# HexaWall-v1.net
KiCad netlist of a schematic drawn in EAGLE
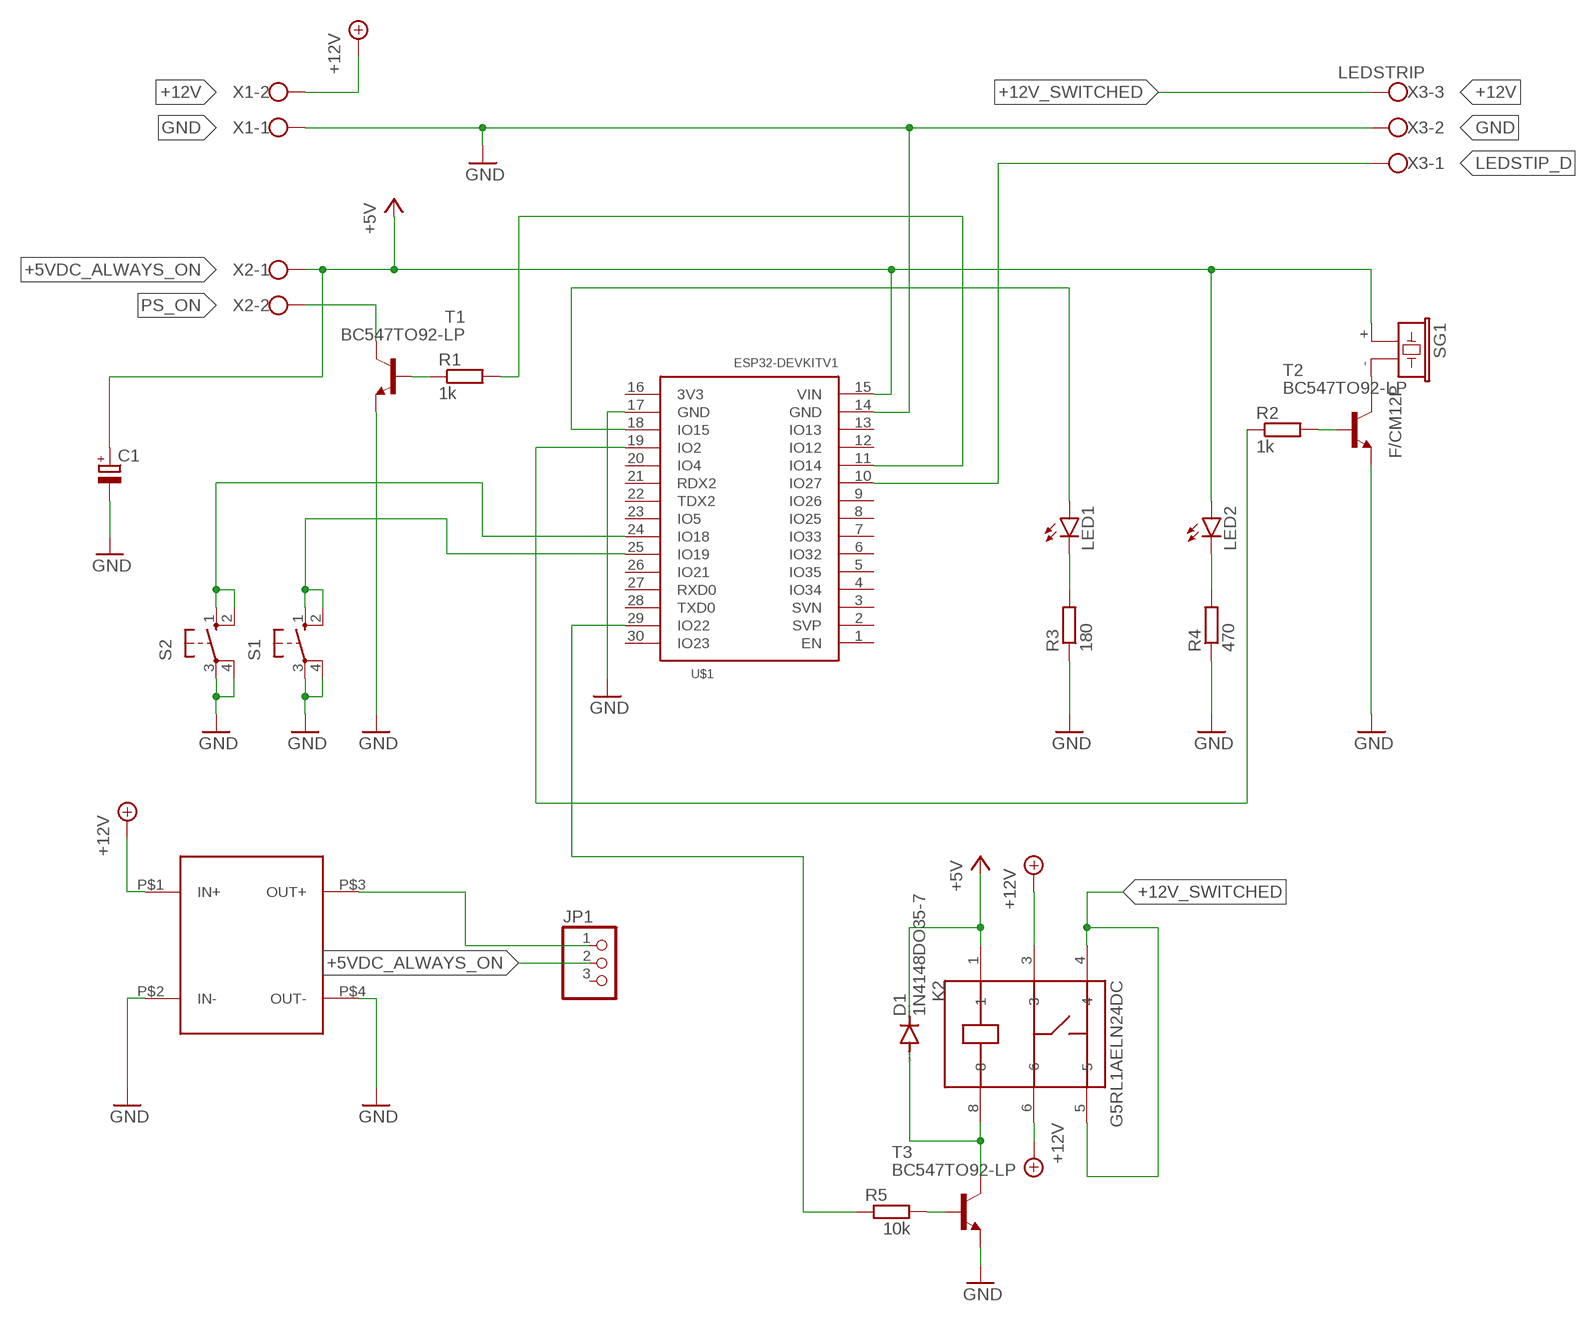
[diagram p0: schematic, sheet 1]

(export (version "E")
  (design (tool "Eeschema 10.0.6"))
  (components
    (comp (ref "C1")
      (value "CPOL-EUE10-20")
      (footprint "eagle-import:EB20D")
      (libsource (lib "eagle-import") (part "CPOL-EUE10-20"))
    )
    (comp (ref "D1")
      (value "1N4148DO35-7")
      (footprint "eagle-import:DO35-7")
      (fields (field (name "SPICEPREFIX") "D"))
      (libsource (lib "eagle-import") (part "1N4148DO35-7"))
    )
    (comp (ref "JP1")
      (value "PINHD-1X3")
      (footprint "eagle-import:1X03")
      (libsource (lib "eagle-import") (part "PINHD-1X3"))
    )
    (comp (ref "K2")
      (value "G5RL1AELN24DC")
      (footprint "eagle-import:G5RL-1-E-HR")
      (fields (field (name "SPICEPREFIX") "X"))
      (libsource (lib "eagle-import") (part "G5RL1AELN24DC"))
    )
    (comp (ref "LED1")
      (value "LED5MM")
      (footprint "eagle-import:LED5MM")
      (libsource (lib "eagle-import") (part "LED5MM"))
    )
    (comp (ref "LED2")
      (value "LED5MM")
      (footprint "eagle-import:LED5MM")
      (libsource (lib "eagle-import") (part "LED5MM"))
    )
    (comp (ref "PS$1")
      (value "DC/DC_PCB")
      (footprint "eagle-import:DC_DC_PCB")
      (libsource (lib "eagle-import") (part "DC/DC_PCB"))
    )
    (comp (ref "R1")
      (value "1k")
      (footprint "eagle-import:0204_7")
      (libsource (lib "eagle-import") (part "R-EU_0204/7"))
    )
    (comp (ref "R2")
      (value "1k")
      (footprint "eagle-import:0204_7")
      (libsource (lib "eagle-import") (part "R-EU_0204/7"))
    )
    (comp (ref "R3")
      (value "180")
      (footprint "eagle-import:0204_7")
      (libsource (lib "eagle-import") (part "R-EU_0204/7"))
    )
    (comp (ref "R4")
      (value "470")
      (footprint "eagle-import:0204_7")
      (libsource (lib "eagle-import") (part "R-EU_0204/7"))
    )
    (comp (ref "R5")
      (value "10k")
      (footprint "eagle-import:0204_7")
      (libsource (lib "eagle-import") (part "R-EU_0204/7"))
    )
    (comp (ref "S1")
      (value "40-XX")
      (footprint "eagle-import:B3F-40XX")
      (fields (field (name "MF") "OMRON COMPONENTS USA") (field (name "MPN") "B3F-4000"))
      (libsource (lib "eagle-import") (part "40-XX"))
    )
    (comp (ref "S2")
      (value "40-XX")
      (footprint "eagle-import:B3F-40XX")
      (fields (field (name "MF") "OMRON COMPONENTS USA") (field (name "MPN") "B3F-4000"))
      (libsource (lib "eagle-import") (part "40-XX"))
    )
    (comp (ref "SG1")
      (value "F/CM12P")
      (footprint "eagle-import:F_CM12P")
      (libsource (lib "eagle-import") (part "F/CM12P"))
    )
    (comp (ref "T1")
      (value "BC547TO92-LP")
      (footprint "eagle-import:TO92-CBE")
      (libsource (lib "eagle-import") (part "BC547TO92-LP"))
    )
    (comp (ref "T2")
      (value "BC547TO92-LP")
      (footprint "eagle-import:TO92-CBE")
      (libsource (lib "eagle-import") (part "BC547TO92-LP"))
    )
    (comp (ref "T3")
      (value "BC547TO92-LP")
      (footprint "eagle-import:TO92-CBE")
      (fields (field (name "SPICEPREFIX") "J"))
      (libsource (lib "eagle-import") (part "BC547TO92-LP"))
    )
    (comp (ref "U$1")
      (value "ESP32DEVKITV1")
      (footprint "eagle-import:ESP32-DEVKITV1")
      (libsource (lib "eagle-import") (part "ESP32DEVKITV1"))
    )
    (comp (ref "X1")
      (value "W237-102")
      (footprint "eagle-import:W237-102")
      (fields (field (name "MPN") "237-102"))
      (libsource (lib "eagle-import") (part "W237-102"))
    )
    (comp (ref "X2")
      (value "W237-102")
      (footprint "eagle-import:W237-102")
      (fields (field (name "MPN") "237-102"))
      (libsource (lib "eagle-import") (part "W237-102"))
    )
    (comp (ref "X3")
      (value "LEDSTRIP")
      (footprint "eagle-import:W237-103")
      (fields (field (name "MPN") "237-103"))
      (libsource (lib "eagle-import") (part "W237-103"))
    )
  )
  (nets
    (net (code "1") (name "+5VDC_ALWAYS_ON") (class "Default")
      (node (ref "C1") (pin "+") (pinfunction "+_+") (pintype "passive"))
      (node (ref "D1") (pin "C") (pinfunction "C_C") (pintype "passive"))
      (node (ref "JP1") (pin "2") (pinfunction "2_2") (pintype "passive"))
      (node (ref "K2") (pin "1") (pinfunction "1_1") (pintype "passive"))
      (node (ref "LED2") (pin "A") (pinfunction "A_A") (pintype "passive"))
      (node (ref "SG1") (pin "+") (pinfunction "1_+") (pintype "passive"))
      (node (ref "U$1") (pin "15") (pinfunction "VIN_15") (pintype "bidirectional"))
      (node (ref "X2") (pin "1") (pinfunction "KL_1") (pintype "passive"))
    )
    (net (code "2") (name "+12V") (class "Default")
      (node (ref "K2") (pin "3") (pinfunction "3_3") (pintype "passive"))
      (node (ref "K2") (pin "6") (pinfunction "6_6") (pintype "passive"))
      (node (ref "PS$1") (pin "P$1") (pinfunction "IN+_P$1") (pintype "input"))
      (node (ref "X1") (pin "2") (pinfunction "KL_2") (pintype "passive"))
    )
    (net (code "3") (name "+12V_SWITCHED") (class "Default")
      (node (ref "K2") (pin "4") (pinfunction "4_4") (pintype "passive"))
      (node (ref "K2") (pin "5") (pinfunction "5_5") (pintype "passive"))
      (node (ref "X3") (pin "3") (pinfunction "KL_3") (pintype "passive"))
    )
    (net (code "4") (name "GND") (class "Default")
      (node (ref "C1") (pin "-") (pinfunction "-_-") (pintype "passive"))
      (node (ref "PS$1") (pin "P$2") (pinfunction "IN-_P$2") (pintype "bidirectional"))
      (node (ref "PS$1") (pin "P$4") (pinfunction "OUT-_P$4") (pintype "output"))
      (node (ref "R3") (pin "1") (pinfunction "1_1") (pintype "passive"))
      (node (ref "R4") (pin "1") (pinfunction "1_1") (pintype "passive"))
      (node (ref "S1") (pin "3") (pinfunction "P_3") (pintype "passive"))
      (node (ref "S1") (pin "4") (pinfunction "P1_4") (pintype "passive"))
      (node (ref "S2") (pin "3") (pinfunction "P_3") (pintype "passive"))
      (node (ref "S2") (pin "4") (pinfunction "P1_4") (pintype "passive"))
      (node (ref "T1") (pin "E") (pinfunction "E_E") (pintype "passive"))
      (node (ref "T2") (pin "E") (pinfunction "E_E") (pintype "passive"))
      (node (ref "T3") (pin "E") (pinfunction "E_E") (pintype "passive"))
      (node (ref "U$1") (pin "14") (pinfunction "GND_14") (pintype "bidirectional"))
      (node (ref "U$1") (pin "17") (pinfunction "GND_17") (pintype "bidirectional"))
      (node (ref "X1") (pin "1") (pinfunction "KL_1") (pintype "passive"))
      (node (ref "X3") (pin "2") (pinfunction "KL_2") (pintype "passive"))
    )
    (net (code "5") (name "LEDSTIP_D") (class "Default")
      (node (ref "U$1") (pin "10") (pinfunction "IO27_10") (pintype "bidirectional"))
      (node (ref "X3") (pin "1") (pinfunction "KL_1") (pintype "passive"))
    )
    (net (code "6") (name "Net-(D1-PadA)") (class "Default")
      (node (ref "D1") (pin "A") (pinfunction "A_A") (pintype "passive"))
      (node (ref "K2") (pin "8") (pinfunction "8_8") (pintype "passive"))
      (node (ref "T3") (pin "C") (pinfunction "C_C") (pintype "passive"))
    )
    (net (code "7") (name "Net-(LED1-C)") (class "Default")
      (node (ref "LED1") (pin "K") (pinfunction "C_K") (pintype "passive"))
      (node (ref "R3") (pin "2") (pinfunction "2_2") (pintype "passive"))
    )
    (net (code "8") (name "Net-(LED2-C)") (class "Default")
      (node (ref "LED2") (pin "K") (pinfunction "C_K") (pintype "passive"))
      (node (ref "R4") (pin "2") (pinfunction "2_2") (pintype "passive"))
    )
    (net (code "9") (name "Net-(PS$1-OUT+)") (class "Default")
      (node (ref "JP1") (pin "1") (pinfunction "1_1") (pintype "passive"))
      (node (ref "PS$1") (pin "P$3") (pinfunction "OUT+_P$3") (pintype "bidirectional"))
    )
    (net (code "10") (name "Net-(R1-Pad1)") (class "Default")
      (node (ref "R1") (pin "1") (pinfunction "1_1") (pintype "passive"))
      (node (ref "T1") (pin "B") (pinfunction "B_B") (pintype "passive"))
    )
    (net (code "11") (name "Net-(R2-Pad2)") (class "Default")
      (node (ref "R2") (pin "2") (pinfunction "2_2") (pintype "passive"))
      (node (ref "T2") (pin "B") (pinfunction "B_B") (pintype "passive"))
    )
    (net (code "12") (name "Net-(R5-Pad2)") (class "Default")
      (node (ref "R5") (pin "2") (pinfunction "2_2") (pintype "passive"))
      (node (ref "T3") (pin "B") (pinfunction "B_B") (pintype "passive"))
    )
    (net (code "13") (name "Net-(S1-S)") (class "Default")
      (node (ref "S1") (pin "1") (pinfunction "S_1") (pintype "passive"))
      (node (ref "S1") (pin "2") (pinfunction "S1_2") (pintype "passive"))
      (node (ref "U$1") (pin "25") (pinfunction "IO19_25") (pintype "bidirectional"))
    )
    (net (code "14") (name "Net-(S2-S)") (class "Default")
      (node (ref "S2") (pin "1") (pinfunction "S_1") (pintype "passive"))
      (node (ref "S2") (pin "2") (pinfunction "S1_2") (pintype "passive"))
      (node (ref "U$1") (pin "24") (pinfunction "IO18_24") (pintype "bidirectional"))
    )
    (net (code "15") (name "Net-(SG1-2)") (class "Default")
      (node (ref "SG1") (pin "-") (pinfunction "2_-") (pintype "passive"))
      (node (ref "T2") (pin "C") (pinfunction "C_C") (pintype "passive"))
    )
    (net (code "16") (name "Net-(U$1-IO2)") (class "Default")
      (node (ref "R2") (pin "1") (pinfunction "1_1") (pintype "passive"))
      (node (ref "U$1") (pin "19") (pinfunction "IO2_19") (pintype "bidirectional"))
    )
    (net (code "17") (name "Net-(U$1-IO14)") (class "Default")
      (node (ref "R1") (pin "2") (pinfunction "2_2") (pintype "passive"))
      (node (ref "U$1") (pin "11") (pinfunction "IO14_11") (pintype "bidirectional"))
    )
    (net (code "18") (name "Net-(U$1-IO15)") (class "Default")
      (node (ref "LED1") (pin "A") (pinfunction "A_A") (pintype "passive"))
      (node (ref "U$1") (pin "18") (pinfunction "IO15_18") (pintype "bidirectional"))
    )
    (net (code "19") (name "Net-(U$1-IO22)") (class "Default")
      (node (ref "R5") (pin "1") (pinfunction "1_1") (pintype "passive"))
      (node (ref "U$1") (pin "29") (pinfunction "IO22_29") (pintype "bidirectional"))
    )
    (net (code "20") (name "PS_ON") (class "Default")
      (node (ref "T1") (pin "C") (pinfunction "C_C") (pintype "passive"))
      (node (ref "X2") (pin "2") (pinfunction "KL_2") (pintype "passive"))
    )
    (net (code "21") (name "unconnected-(JP1-Pad3)") (class "Default")
      (node (ref "JP1") (pin "3") (pinfunction "3_3") (pintype "passive"))
    )
    (net (code "22") (name "unconnected-(U$1-3V3-Pad16)") (class "Default")
      (node (ref "U$1") (pin "16") (pinfunction "3V3_16") (pintype "bidirectional"))
    )
    (net (code "23") (name "unconnected-(U$1-EN-Pad1)") (class "Default")
      (node (ref "U$1") (pin "1") (pinfunction "EN_1") (pintype "bidirectional"))
    )
    (net (code "24") (name "unconnected-(U$1-IO4-Pad20)") (class "Default")
      (node (ref "U$1") (pin "20") (pinfunction "IO4_20") (pintype "bidirectional"))
    )
    (net (code "25") (name "unconnected-(U$1-IO5-Pad23)") (class "Default")
      (node (ref "U$1") (pin "23") (pinfunction "IO5_23") (pintype "bidirectional"))
    )
    (net (code "26") (name "unconnected-(U$1-IO12-Pad12)") (class "Default")
      (node (ref "U$1") (pin "12") (pinfunction "IO12_12") (pintype "bidirectional"))
    )
    (net (code "27") (name "unconnected-(U$1-IO13-Pad13)") (class "Default")
      (node (ref "U$1") (pin "13") (pinfunction "IO13_13") (pintype "bidirectional"))
    )
    (net (code "28") (name "unconnected-(U$1-IO21-Pad26)") (class "Default")
      (node (ref "U$1") (pin "26") (pinfunction "IO21_26") (pintype "bidirectional"))
    )
    (net (code "29") (name "unconnected-(U$1-IO23-Pad30)") (class "Default")
      (node (ref "U$1") (pin "30") (pinfunction "IO23_30") (pintype "bidirectional"))
    )
    (net (code "30") (name "unconnected-(U$1-IO25-Pad8)") (class "Default")
      (node (ref "U$1") (pin "8") (pinfunction "IO25_8") (pintype "bidirectional"))
    )
    (net (code "31") (name "unconnected-(U$1-IO26-Pad9)") (class "Default")
      (node (ref "U$1") (pin "9") (pinfunction "IO26_9") (pintype "bidirectional"))
    )
    (net (code "32") (name "unconnected-(U$1-IO32-Pad6)") (class "Default")
      (node (ref "U$1") (pin "6") (pinfunction "IO32_6") (pintype "bidirectional"))
    )
    (net (code "33") (name "unconnected-(U$1-IO33-Pad7)") (class "Default")
      (node (ref "U$1") (pin "7") (pinfunction "IO33_7") (pintype "bidirectional"))
    )
    (net (code "34") (name "unconnected-(U$1-IO34-Pad4)") (class "Default")
      (node (ref "U$1") (pin "4") (pinfunction "IO34_4") (pintype "bidirectional"))
    )
    (net (code "35") (name "unconnected-(U$1-IO35-Pad5)") (class "Default")
      (node (ref "U$1") (pin "5") (pinfunction "IO35_5") (pintype "bidirectional"))
    )
    (net (code "36") (name "unconnected-(U$1-RDX2-Pad21)") (class "Default")
      (node (ref "U$1") (pin "21") (pinfunction "RDX2_21") (pintype "bidirectional"))
    )
    (net (code "37") (name "unconnected-(U$1-RXD0-Pad27)") (class "Default")
      (node (ref "U$1") (pin "27") (pinfunction "RXD0_27") (pintype "bidirectional"))
    )
    (net (code "38") (name "unconnected-(U$1-SVN-Pad3)") (class "Default")
      (node (ref "U$1") (pin "3") (pinfunction "SVN_3") (pintype "bidirectional"))
    )
    (net (code "39") (name "unconnected-(U$1-SVP-Pad2)") (class "Default")
      (node (ref "U$1") (pin "2") (pinfunction "SVP_2") (pintype "bidirectional"))
    )
    (net (code "40") (name "unconnected-(U$1-TDX2-Pad22)") (class "Default")
      (node (ref "U$1") (pin "22") (pinfunction "TDX2_22") (pintype "bidirectional"))
    )
    (net (code "41") (name "unconnected-(U$1-TXD0-Pad28)") (class "Default")
      (node (ref "U$1") (pin "28") (pinfunction "TXD0_28") (pintype "bidirectional"))
    )
  )
)
